# untitled.net
KiCad netlist of a schematic drawn in EAGLE
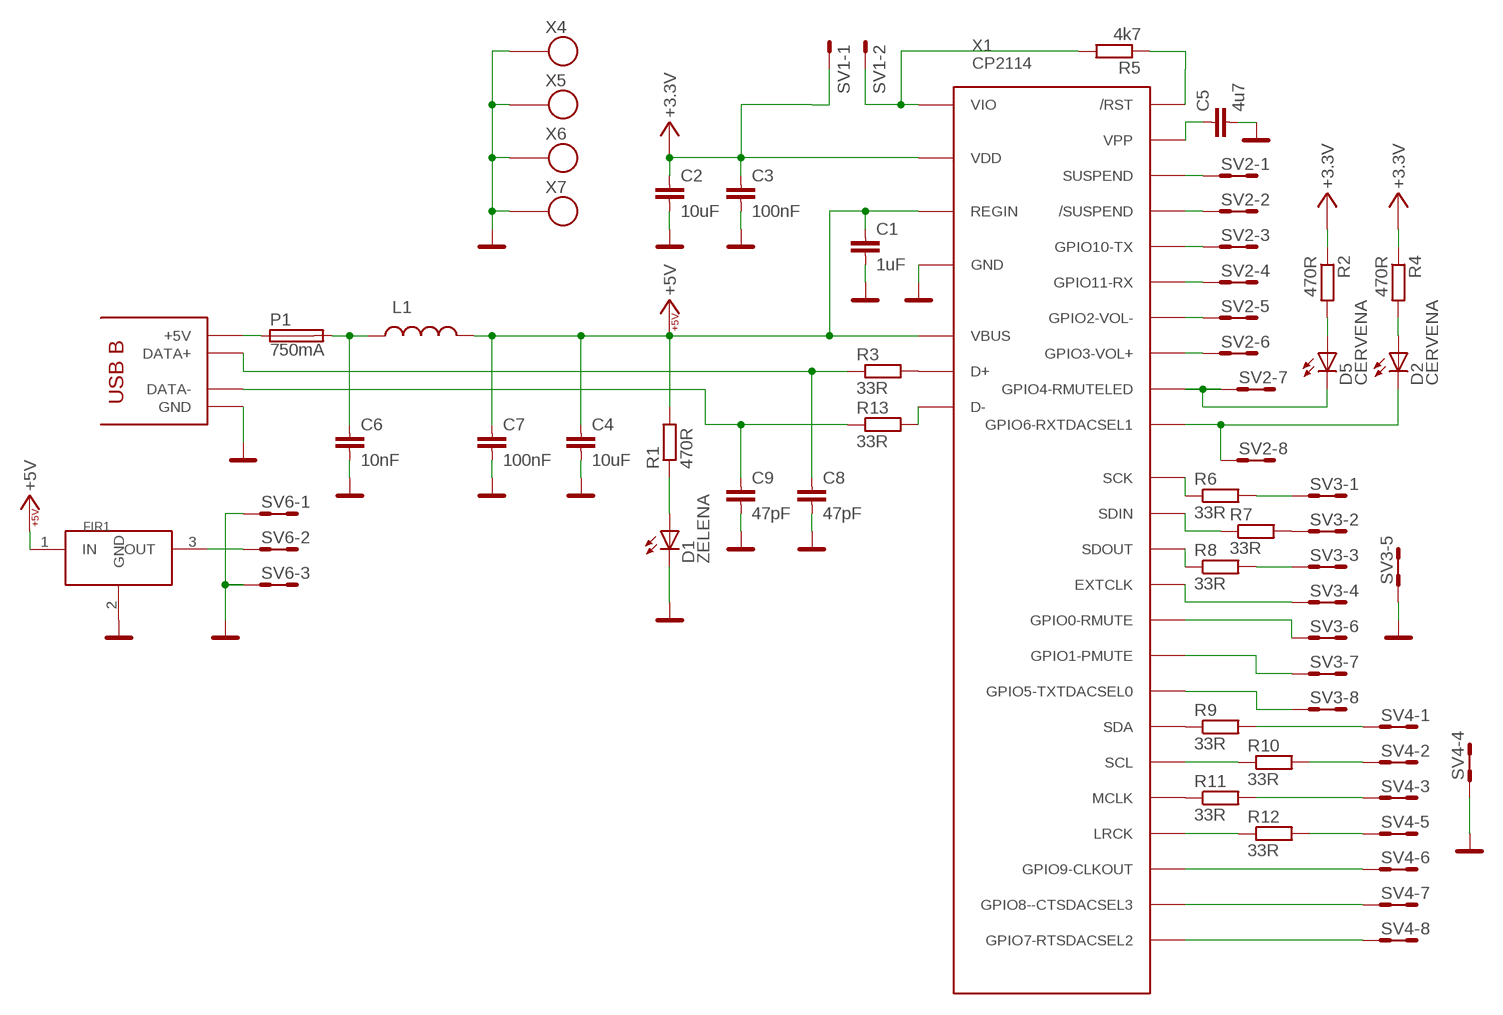
[diagram p0: schematic, sheet 1]

(export (version "E")
  (design (tool "Eeschema 10.0.6"))
  (components
    (comp (ref "C1")
      (value "1uF")
      (footprint "eagle-import:C0805")
      (libsource (lib "eagle-import") (part "C0805"))
    )
    (comp (ref "C2")
      (value "10uF")
      (footprint "eagle-import:C0805")
      (libsource (lib "eagle-import") (part "C0805"))
    )
    (comp (ref "C3")
      (value "100nF")
      (footprint "eagle-import:C0805")
      (libsource (lib "eagle-import") (part "C0805"))
    )
    (comp (ref "C4")
      (value "10uF")
      (footprint "eagle-import:C0805")
      (libsource (lib "eagle-import") (part "C0805"))
    )
    (comp (ref "C5")
      (value "4u7")
      (footprint "eagle-import:C0805")
      (libsource (lib "eagle-import") (part "C0805"))
    )
    (comp (ref "C6")
      (value "10nF")
      (footprint "eagle-import:C0805")
      (libsource (lib "eagle-import") (part "C0805"))
    )
    (comp (ref "C7")
      (value "100nF")
      (footprint "eagle-import:C0805")
      (libsource (lib "eagle-import") (part "C0805"))
    )
    (comp (ref "C8")
      (value "47pF")
      (footprint "eagle-import:C0805")
      (libsource (lib "eagle-import") (part "C0805"))
    )
    (comp (ref "C9")
      (value "47pF")
      (footprint "eagle-import:C0805")
      (libsource (lib "eagle-import") (part "C0805"))
    )
    (comp (ref "D1")
      (value "ZELENA")
      (footprint "eagle-import:1206_2")
      (libsource (lib "eagle-import") (part "LED1206_2"))
    )
    (comp (ref "D2")
      (value "CERVENA")
      (footprint "eagle-import:1206_2")
      (libsource (lib "eagle-import") (part "LED1206_2"))
    )
    (comp (ref "D5")
      (value "CERVENA")
      (footprint "eagle-import:1206_2")
      (libsource (lib "eagle-import") (part "LED1206_2"))
    )
    (comp (ref "FIR1")
      (value "FILTR0805")
      (footprint "eagle-import:F0805")
      (libsource (lib "eagle-import") (part "FILTR0805"))
    )
    (comp (ref "L1")
      (value "L0805")
      (footprint "eagle-import:L0805")
      (libsource (lib "eagle-import") (part "L0805"))
    )
    (comp (ref "P1")
      (value "750mA")
      (footprint "eagle-import:1812")
      (libsource (lib "eagle-import") (part "POJISTKA_1812"))
    )
    (comp (ref "R1")
      (value "470R")
      (footprint "eagle-import:0805")
      (libsource (lib "eagle-import") (part "R0805"))
    )
    (comp (ref "R2")
      (value "470R")
      (footprint "eagle-import:0805")
      (libsource (lib "eagle-import") (part "R0805"))
    )
    (comp (ref "R3")
      (value "33R")
      (footprint "eagle-import:0805")
      (libsource (lib "eagle-import") (part "R0805"))
    )
    (comp (ref "R4")
      (value "470R")
      (footprint "eagle-import:0805")
      (libsource (lib "eagle-import") (part "R0805"))
    )
    (comp (ref "R5")
      (value "4k7")
      (footprint "eagle-import:0805")
      (libsource (lib "eagle-import") (part "R0805"))
    )
    (comp (ref "R6")
      (value "33R")
      (footprint "eagle-import:0805")
      (libsource (lib "eagle-import") (part "R0805"))
    )
    (comp (ref "R7")
      (value "33R")
      (footprint "eagle-import:0805")
      (libsource (lib "eagle-import") (part "R0805"))
    )
    (comp (ref "R8")
      (value "33R")
      (footprint "eagle-import:0805")
      (libsource (lib "eagle-import") (part "R0805"))
    )
    (comp (ref "R9")
      (value "33R")
      (footprint "eagle-import:0805")
      (libsource (lib "eagle-import") (part "R0805"))
    )
    (comp (ref "R10")
      (value "33R")
      (footprint "eagle-import:0805")
      (libsource (lib "eagle-import") (part "R0805"))
    )
    (comp (ref "R11")
      (value "33R")
      (footprint "eagle-import:0805")
      (libsource (lib "eagle-import") (part "R0805"))
    )
    (comp (ref "R12")
      (value "33R")
      (footprint "eagle-import:0805")
      (libsource (lib "eagle-import") (part "R0805"))
    )
    (comp (ref "R13")
      (value "33R")
      (footprint "eagle-import:0805")
      (libsource (lib "eagle-import") (part "R0805"))
    )
    (comp (ref "SV1")
      (value "MA02-1")
      (footprint "eagle-import:MA02-1")
      (libsource (lib "eagle-import") (part "MA02-1"))
    )
    (comp (ref "SV2")
      (value "MA08-2")
      (footprint "eagle-import:MA08-2")
      (libsource (lib "eagle-import") (part "MA08-2"))
    )
    (comp (ref "SV3")
      (value "MA08-2")
      (footprint "eagle-import:MA08-2")
      (libsource (lib "eagle-import") (part "MA08-2"))
    )
    (comp (ref "SV4")
      (value "MA08-2")
      (footprint "eagle-import:MA08-2")
      (libsource (lib "eagle-import") (part "MA08-2"))
    )
    (comp (ref "SV6")
      (value "MA03-2")
      (footprint "eagle-import:MA03-2")
      (libsource (lib "eagle-import") (part "MA03-2"))
    )
    (comp (ref "X1")
      (value "CP2114")
      (footprint "eagle-import:QFN-32")
      (libsource (lib "eagle-import") (part "CP2114"))
    )
    (comp (ref "X3")
      (value "USB_B")
      (footprint "eagle-import:USB_B")
      (libsource (lib "eagle-import") (part "USB_B"))
    )
    (comp (ref "X4")
      (value "SROUB3M")
      (footprint "eagle-import:SROUB3M")
      (libsource (lib "eagle-import") (part "SROUB3M"))
    )
    (comp (ref "X5")
      (value "SROUB3M")
      (footprint "eagle-import:SROUB3M")
      (libsource (lib "eagle-import") (part "SROUB3M"))
    )
    (comp (ref "X6")
      (value "SROUB3M")
      (footprint "eagle-import:SROUB3M")
      (libsource (lib "eagle-import") (part "SROUB3M"))
    )
    (comp (ref "X7")
      (value "SROUB3M")
      (footprint "eagle-import:SROUB3M")
      (libsource (lib "eagle-import") (part "SROUB3M"))
    )
  )
  (nets
    (net (code "1") (name "+3.3V") (class "Default")
      (node (ref "C2") (pin "1") (pinfunction "1_1") (pintype "passive"))
      (node (ref "C3") (pin "1") (pinfunction "1_1") (pintype "passive"))
      (node (ref "R2") (pin "1") (pinfunction "1_1") (pintype "passive"))
      (node (ref "R4") (pin "1") (pinfunction "1_1") (pintype "passive"))
      (node (ref "SV1") (pin "1") (pinfunction "P$1_1") (pintype "passive"))
      (node (ref "X1") (pin "7") (pinfunction "VDD_7") (pintype "bidirectional"))
    )
    (net (code "2") (name "+5V") (class "Default")
      (node (ref "C1") (pin "1") (pinfunction "1_1") (pintype "passive"))
      (node (ref "C4") (pin "1") (pinfunction "1_1") (pintype "passive"))
      (node (ref "C7") (pin "1") (pinfunction "1_1") (pintype "passive"))
      (node (ref "FIR1") (pin "1") (pinfunction "IN_1") (pintype "bidirectional"))
      (node (ref "L1") (pin "2") (pinfunction "2_2") (pintype "passive"))
      (node (ref "R1") (pin "2") (pinfunction "2_2") (pintype "passive"))
      (node (ref "X1") (pin "8") (pinfunction "REGIN_8") (pintype "bidirectional"))
      (node (ref "X1") (pin "9") (pinfunction "VBUS_9") (pintype "bidirectional"))
    )
    (net (code "3") (name "GND") (class "Default")
      (node (ref "C1") (pin "2") (pinfunction "2_2") (pintype "passive"))
      (node (ref "C2") (pin "2") (pinfunction "2_2") (pintype "passive"))
      (node (ref "C3") (pin "2") (pinfunction "2_2") (pintype "passive"))
      (node (ref "C4") (pin "2") (pinfunction "2_2") (pintype "passive"))
      (node (ref "C5") (pin "2") (pinfunction "2_2") (pintype "passive"))
      (node (ref "C6") (pin "2") (pinfunction "2_2") (pintype "passive"))
      (node (ref "C7") (pin "2") (pinfunction "2_2") (pintype "passive"))
      (node (ref "C8") (pin "2") (pinfunction "2_2") (pintype "passive"))
      (node (ref "C9") (pin "2") (pinfunction "2_2") (pintype "passive"))
      (node (ref "D1") (pin "K") (pinfunction "C_K") (pintype "passive"))
      (node (ref "FIR1") (pin "2") (pinfunction "GND_2") (pintype "passive"))
      (node (ref "SV3") (pin "10") (pinfunction "K_10") (pintype "passive"))
      (node (ref "SV3") (pin "9") (pinfunction "K_9") (pintype "passive"))
      (node (ref "SV4") (pin "7") (pinfunction "K_7") (pintype "passive"))
      (node (ref "SV4") (pin "8") (pinfunction "K_8") (pintype "passive"))
      (node (ref "SV6") (pin "1") (pinfunction "K_1") (pintype "passive"))
      (node (ref "SV6") (pin "2") (pinfunction "K_2") (pintype "passive"))
      (node (ref "SV6") (pin "5") (pinfunction "K_5") (pintype "passive"))
      (node (ref "SV6") (pin "6") (pinfunction "K_6") (pintype "passive"))
      (node (ref "X1") (pin "3") (pinfunction "GND_3") (pintype "bidirectional"))
      (node (ref "X1") (pin "EXP") (pinfunction "GND_EXP") (pintype "bidirectional"))
      (node (ref "X3") (pin "4") (pinfunction "GND_4") (pintype "bidirectional"))
      (node (ref "X3") (pin "GND") (pinfunction "GND_GND") (pintype "bidirectional"))
      (node (ref "X3") (pin "GND2") (pinfunction "GND_GND2") (pintype "bidirectional"))
      (node (ref "X4") (pin "P$1") (pinfunction "P$1_P$1") (pintype "bidirectional"))
      (node (ref "X5") (pin "P$1") (pinfunction "P$1_P$1") (pintype "bidirectional"))
      (node (ref "X6") (pin "P$1") (pinfunction "P$1_P$1") (pintype "bidirectional"))
      (node (ref "X7") (pin "P$1") (pinfunction "P$1_P$1") (pintype "bidirectional"))
    )
    (net (code "4") (name "Net-(C6-Pad1)") (class "Default")
      (node (ref "C6") (pin "1") (pinfunction "1_1") (pintype "passive"))
      (node (ref "L1") (pin "1") (pinfunction "1_1") (pintype "passive"))
      (node (ref "P1") (pin "2") (pinfunction "2_2") (pintype "passive"))
    )
    (net (code "5") (name "Net-(D1-PadA)") (class "Default")
      (node (ref "D1") (pin "A") (pinfunction "A_A") (pintype "passive"))
      (node (ref "R1") (pin "1") (pinfunction "1_1") (pintype "passive"))
    )
    (net (code "6") (name "Net-(D2-C)") (class "Default")
      (node (ref "D2") (pin "K") (pinfunction "C_K") (pintype "passive"))
      (node (ref "SV2") (pin "15") (pinfunction "K_15") (pintype "passive"))
      (node (ref "SV2") (pin "16") (pinfunction "K_16") (pintype "passive"))
      (node (ref "X1") (pin "11") (pinfunction "GPIO6-RXTDACSEL1_11") (pintype "bidirectional"))
    )
    (net (code "7") (name "Net-(D2-PadA)") (class "Default")
      (node (ref "D2") (pin "A") (pinfunction "A_A") (pintype "passive"))
      (node (ref "R4") (pin "2") (pinfunction "2_2") (pintype "passive"))
    )
    (net (code "8") (name "Net-(D5-C)") (class "Default")
      (node (ref "D5") (pin "K") (pinfunction "C_K") (pintype "passive"))
      (node (ref "SV2") (pin "13") (pinfunction "K_13") (pintype "passive"))
      (node (ref "SV2") (pin "14") (pinfunction "K_14") (pintype "passive"))
      (node (ref "X1") (pin "12") (pinfunction "GPIO4-RMUTELED_12") (pintype "bidirectional"))
    )
    (net (code "9") (name "Net-(D5-PadA)") (class "Default")
      (node (ref "D5") (pin "A") (pinfunction "A_A") (pintype "passive"))
      (node (ref "R2") (pin "2") (pinfunction "2_2") (pintype "passive"))
    )
    (net (code "10") (name "Net-(FIR1-OUT)") (class "Default")
      (node (ref "FIR1") (pin "3") (pinfunction "OUT_3") (pintype "bidirectional"))
      (node (ref "SV6") (pin "3") (pinfunction "K_3") (pintype "passive"))
      (node (ref "SV6") (pin "4") (pinfunction "K_4") (pintype "passive"))
    )
    (net (code "11") (name "Net-(R6-Pad2)") (class "Default")
      (node (ref "R6") (pin "2") (pinfunction "2_2") (pintype "passive"))
      (node (ref "SV3") (pin "1") (pinfunction "K_1") (pintype "passive"))
      (node (ref "SV3") (pin "2") (pinfunction "K_2") (pintype "passive"))
    )
    (net (code "12") (name "Net-(R7-Pad2)") (class "Default")
      (node (ref "R7") (pin "2") (pinfunction "2_2") (pintype "passive"))
      (node (ref "SV3") (pin "3") (pinfunction "K_3") (pintype "passive"))
      (node (ref "SV3") (pin "4") (pinfunction "K_4") (pintype "passive"))
    )
    (net (code "13") (name "Net-(R8-Pad2)") (class "Default")
      (node (ref "R8") (pin "2") (pinfunction "2_2") (pintype "passive"))
      (node (ref "SV3") (pin "5") (pinfunction "K_5") (pintype "passive"))
      (node (ref "SV3") (pin "6") (pinfunction "K_6") (pintype "passive"))
    )
    (net (code "14") (name "Net-(R9-Pad2)") (class "Default")
      (node (ref "R9") (pin "2") (pinfunction "2_2") (pintype "passive"))
      (node (ref "SV4") (pin "1") (pinfunction "K_1") (pintype "passive"))
      (node (ref "SV4") (pin "2") (pinfunction "K_2") (pintype "passive"))
    )
    (net (code "15") (name "Net-(R10-Pad2)") (class "Default")
      (node (ref "R10") (pin "2") (pinfunction "2_2") (pintype "passive"))
      (node (ref "SV4") (pin "3") (pinfunction "K_3") (pintype "passive"))
      (node (ref "SV4") (pin "4") (pinfunction "K_4") (pintype "passive"))
    )
    (net (code "16") (name "Net-(R11-Pad2)") (class "Default")
      (node (ref "R11") (pin "2") (pinfunction "2_2") (pintype "passive"))
      (node (ref "SV4") (pin "5") (pinfunction "K_5") (pintype "passive"))
      (node (ref "SV4") (pin "6") (pinfunction "K_6") (pintype "passive"))
    )
    (net (code "17") (name "Net-(R12-Pad2)") (class "Default")
      (node (ref "R12") (pin "2") (pinfunction "2_2") (pintype "passive"))
      (node (ref "SV4") (pin "10") (pinfunction "K_10") (pintype "passive"))
      (node (ref "SV4") (pin "9") (pinfunction "K_9") (pintype "passive"))
    )
    (net (code "18") (name "Net-(SV1B-P$1)") (class "Default")
      (node (ref "R5") (pin "2") (pinfunction "2_2") (pintype "passive"))
      (node (ref "SV1") (pin "2") (pinfunction "P$1_2") (pintype "passive"))
      (node (ref "X1") (pin "6") (pinfunction "VIO_6") (pintype "bidirectional"))
    )
    (net (code "19") (name "Net-(X1-D+)") (class "Default")
      (node (ref "R3") (pin "2") (pinfunction "2_2") (pintype "passive"))
      (node (ref "X1") (pin "4") (pinfunction "D+_4") (pintype "bidirectional"))
    )
    (net (code "20") (name "Net-(X1-D-)") (class "Default")
      (node (ref "R13") (pin "2") (pinfunction "2_2") (pintype "passive"))
      (node (ref "X1") (pin "5") (pinfunction "D-_5") (pintype "bidirectional"))
    )
    (net (code "21") (name "Net-(X1-EXTCLK)") (class "Default")
      (node (ref "SV3") (pin "7") (pinfunction "K_7") (pintype "passive"))
      (node (ref "SV3") (pin "8") (pinfunction "K_8") (pintype "passive"))
      (node (ref "X1") (pin "31") (pinfunction "EXTCLK_31") (pintype "bidirectional"))
    )
    (net (code "22") (name "Net-(X1-GPIO0-RMUTE)") (class "Default")
      (node (ref "SV3") (pin "11") (pinfunction "K_11") (pintype "passive"))
      (node (ref "SV3") (pin "12") (pinfunction "K_12") (pintype "passive"))
      (node (ref "X1") (pin "30") (pinfunction "GPIO0-RMUTE_30") (pintype "bidirectional"))
    )
    (net (code "23") (name "Net-(X1-GPIO1-PMUTE)") (class "Default")
      (node (ref "SV3") (pin "13") (pinfunction "K_13") (pintype "passive"))
      (node (ref "SV3") (pin "14") (pinfunction "K_14") (pintype "passive"))
      (node (ref "X1") (pin "29") (pinfunction "GPIO1-PMUTE_29") (pintype "bidirectional"))
    )
    (net (code "24") (name "Net-(X1-GPIO2-VOL-)") (class "Default")
      (node (ref "SV2") (pin "10") (pinfunction "K_10") (pintype "passive"))
      (node (ref "SV2") (pin "9") (pinfunction "K_9") (pintype "passive"))
      (node (ref "X1") (pin "14") (pinfunction "GPIO2-VOL-_14") (pintype "bidirectional"))
    )
    (net (code "25") (name "Net-(X1-GPIO3-VOL+)") (class "Default")
      (node (ref "SV2") (pin "11") (pinfunction "K_11") (pintype "passive"))
      (node (ref "SV2") (pin "12") (pinfunction "K_12") (pintype "passive"))
      (node (ref "X1") (pin "13") (pinfunction "GPIO3-VOL+_13") (pintype "bidirectional"))
    )
    (net (code "26") (name "Net-(X1-GPIO5-TXTDACSEL0)") (class "Default")
      (node (ref "SV3") (pin "15") (pinfunction "K_15") (pintype "passive"))
      (node (ref "SV3") (pin "16") (pinfunction "K_16") (pintype "passive"))
      (node (ref "X1") (pin "28") (pinfunction "GPIO5-TXTDACSEL0_28") (pintype "bidirectional"))
    )
    (net (code "27") (name "Net-(X1-GPIO7-RTSDACSEL2)") (class "Default")
      (node (ref "SV4") (pin "15") (pinfunction "K_15") (pintype "passive"))
      (node (ref "SV4") (pin "16") (pinfunction "K_16") (pintype "passive"))
      (node (ref "X1") (pin "19") (pinfunction "GPIO7-RTSDACSEL2_19") (pintype "bidirectional"))
    )
    (net (code "28") (name "Net-(X1-GPIO8--CTSDACSEL3)") (class "Default")
      (node (ref "SV4") (pin "13") (pinfunction "K_13") (pintype "passive"))
      (node (ref "SV4") (pin "14") (pinfunction "K_14") (pintype "passive"))
      (node (ref "X1") (pin "20") (pinfunction "GPIO8--CTSDACSEL3_20") (pintype "bidirectional"))
    )
    (net (code "29") (name "Net-(X1-GPIO9-CLKOUT)") (class "Default")
      (node (ref "SV4") (pin "11") (pinfunction "K_11") (pintype "passive"))
      (node (ref "SV4") (pin "12") (pinfunction "K_12") (pintype "passive"))
      (node (ref "X1") (pin "22") (pinfunction "GPIO9-CLKOUT_22") (pintype "bidirectional"))
    )
    (net (code "30") (name "Net-(X1-GPIO10-TX)") (class "Default")
      (node (ref "SV2") (pin "5") (pinfunction "K_5") (pintype "passive"))
      (node (ref "SV2") (pin "6") (pinfunction "K_6") (pintype "passive"))
      (node (ref "X1") (pin "16") (pinfunction "GPIO10-TX_16") (pintype "bidirectional"))
    )
    (net (code "31") (name "Net-(X1-GPIO11-RX)") (class "Default")
      (node (ref "SV2") (pin "7") (pinfunction "K_7") (pintype "passive"))
      (node (ref "SV2") (pin "8") (pinfunction "K_8") (pintype "passive"))
      (node (ref "X1") (pin "15") (pinfunction "GPIO11-RX_15") (pintype "bidirectional"))
    )
    (net (code "32") (name "Net-(X1-LRCK)") (class "Default")
      (node (ref "R12") (pin "1") (pinfunction "1_1") (pintype "passive"))
      (node (ref "X1") (pin "23") (pinfunction "LRCK_23") (pintype "bidirectional"))
    )
    (net (code "33") (name "Net-(X1-MCLK)") (class "Default")
      (node (ref "R11") (pin "1") (pinfunction "1_1") (pintype "passive"))
      (node (ref "X1") (pin "25") (pinfunction "MCLK_25") (pintype "bidirectional"))
    )
    (net (code "34") (name "Net-(X1-SCK)") (class "Default")
      (node (ref "R6") (pin "1") (pinfunction "1_1") (pintype "passive"))
      (node (ref "X1") (pin "2") (pinfunction "SCK_2") (pintype "bidirectional"))
    )
    (net (code "35") (name "Net-(X1-SCL)") (class "Default")
      (node (ref "R10") (pin "1") (pinfunction "1_1") (pintype "passive"))
      (node (ref "X1") (pin "26") (pinfunction "SCL_26") (pintype "bidirectional"))
    )
    (net (code "36") (name "Net-(X1-SDA)") (class "Default")
      (node (ref "R9") (pin "1") (pinfunction "1_1") (pintype "passive"))
      (node (ref "X1") (pin "27") (pinfunction "SDA_27") (pintype "bidirectional"))
    )
    (net (code "37") (name "Net-(X1-SDIN)") (class "Default")
      (node (ref "R7") (pin "1") (pinfunction "1_1") (pintype "passive"))
      (node (ref "X1") (pin "1") (pinfunction "SDIN_1") (pintype "bidirectional"))
    )
    (net (code "38") (name "Net-(X1-SDOUT)") (class "Default")
      (node (ref "R8") (pin "1") (pinfunction "1_1") (pintype "passive"))
      (node (ref "X1") (pin "32") (pinfunction "SDOUT_32") (pintype "bidirectional"))
    )
    (net (code "39") (name "Net-(X1-SUSPEND)") (class "Default")
      (node (ref "SV2") (pin "1") (pinfunction "K_1") (pintype "passive"))
      (node (ref "SV2") (pin "2") (pinfunction "K_2") (pintype "passive"))
      (node (ref "X1") (pin "18") (pinfunction "SUSPEND_18") (pintype "bidirectional"))
    )
    (net (code "40") (name "Net-(X1-VPP)") (class "Default")
      (node (ref "C5") (pin "1") (pinfunction "1_1") (pintype "passive"))
      (node (ref "X1") (pin "21") (pinfunction "VPP_21") (pintype "bidirectional"))
    )
    (net (code "41") (name "Net-(X1-{slash}RST)") (class "Default")
      (node (ref "R5") (pin "1") (pinfunction "1_1") (pintype "passive"))
      (node (ref "X1") (pin "10") (pinfunction "/RST_10") (pintype "bidirectional"))
    )
    (net (code "42") (name "Net-(X1-{slash}SUSPEND)") (class "Default")
      (node (ref "SV2") (pin "3") (pinfunction "K_3") (pintype "passive"))
      (node (ref "SV2") (pin "4") (pinfunction "K_4") (pintype "passive"))
      (node (ref "X1") (pin "17") (pinfunction "/SUSPEND_17") (pintype "bidirectional"))
    )
    (net (code "43") (name "Net-(X3-+5V)") (class "Default")
      (node (ref "P1") (pin "1") (pinfunction "1_1") (pintype "passive"))
      (node (ref "X3") (pin "1") (pinfunction "+5V_1") (pintype "bidirectional"))
    )
    (net (code "44") (name "Net-(X3-DATA+)") (class "Default")
      (node (ref "C8") (pin "1") (pinfunction "1_1") (pintype "passive"))
      (node (ref "R3") (pin "1") (pinfunction "1_1") (pintype "passive"))
      (node (ref "X3") (pin "3") (pinfunction "DATA+_3") (pintype "bidirectional"))
    )
    (net (code "45") (name "Net-(X3-DATA-)") (class "Default")
      (node (ref "C9") (pin "1") (pinfunction "1_1") (pintype "passive"))
      (node (ref "R13") (pin "1") (pinfunction "1_1") (pintype "passive"))
      (node (ref "X3") (pin "2") (pinfunction "DATA-_2") (pintype "bidirectional"))
    )
  )
)
